# MicrocontrollerBoard_V0_0.net
KiCad netlist of a schematic drawn in EAGLE
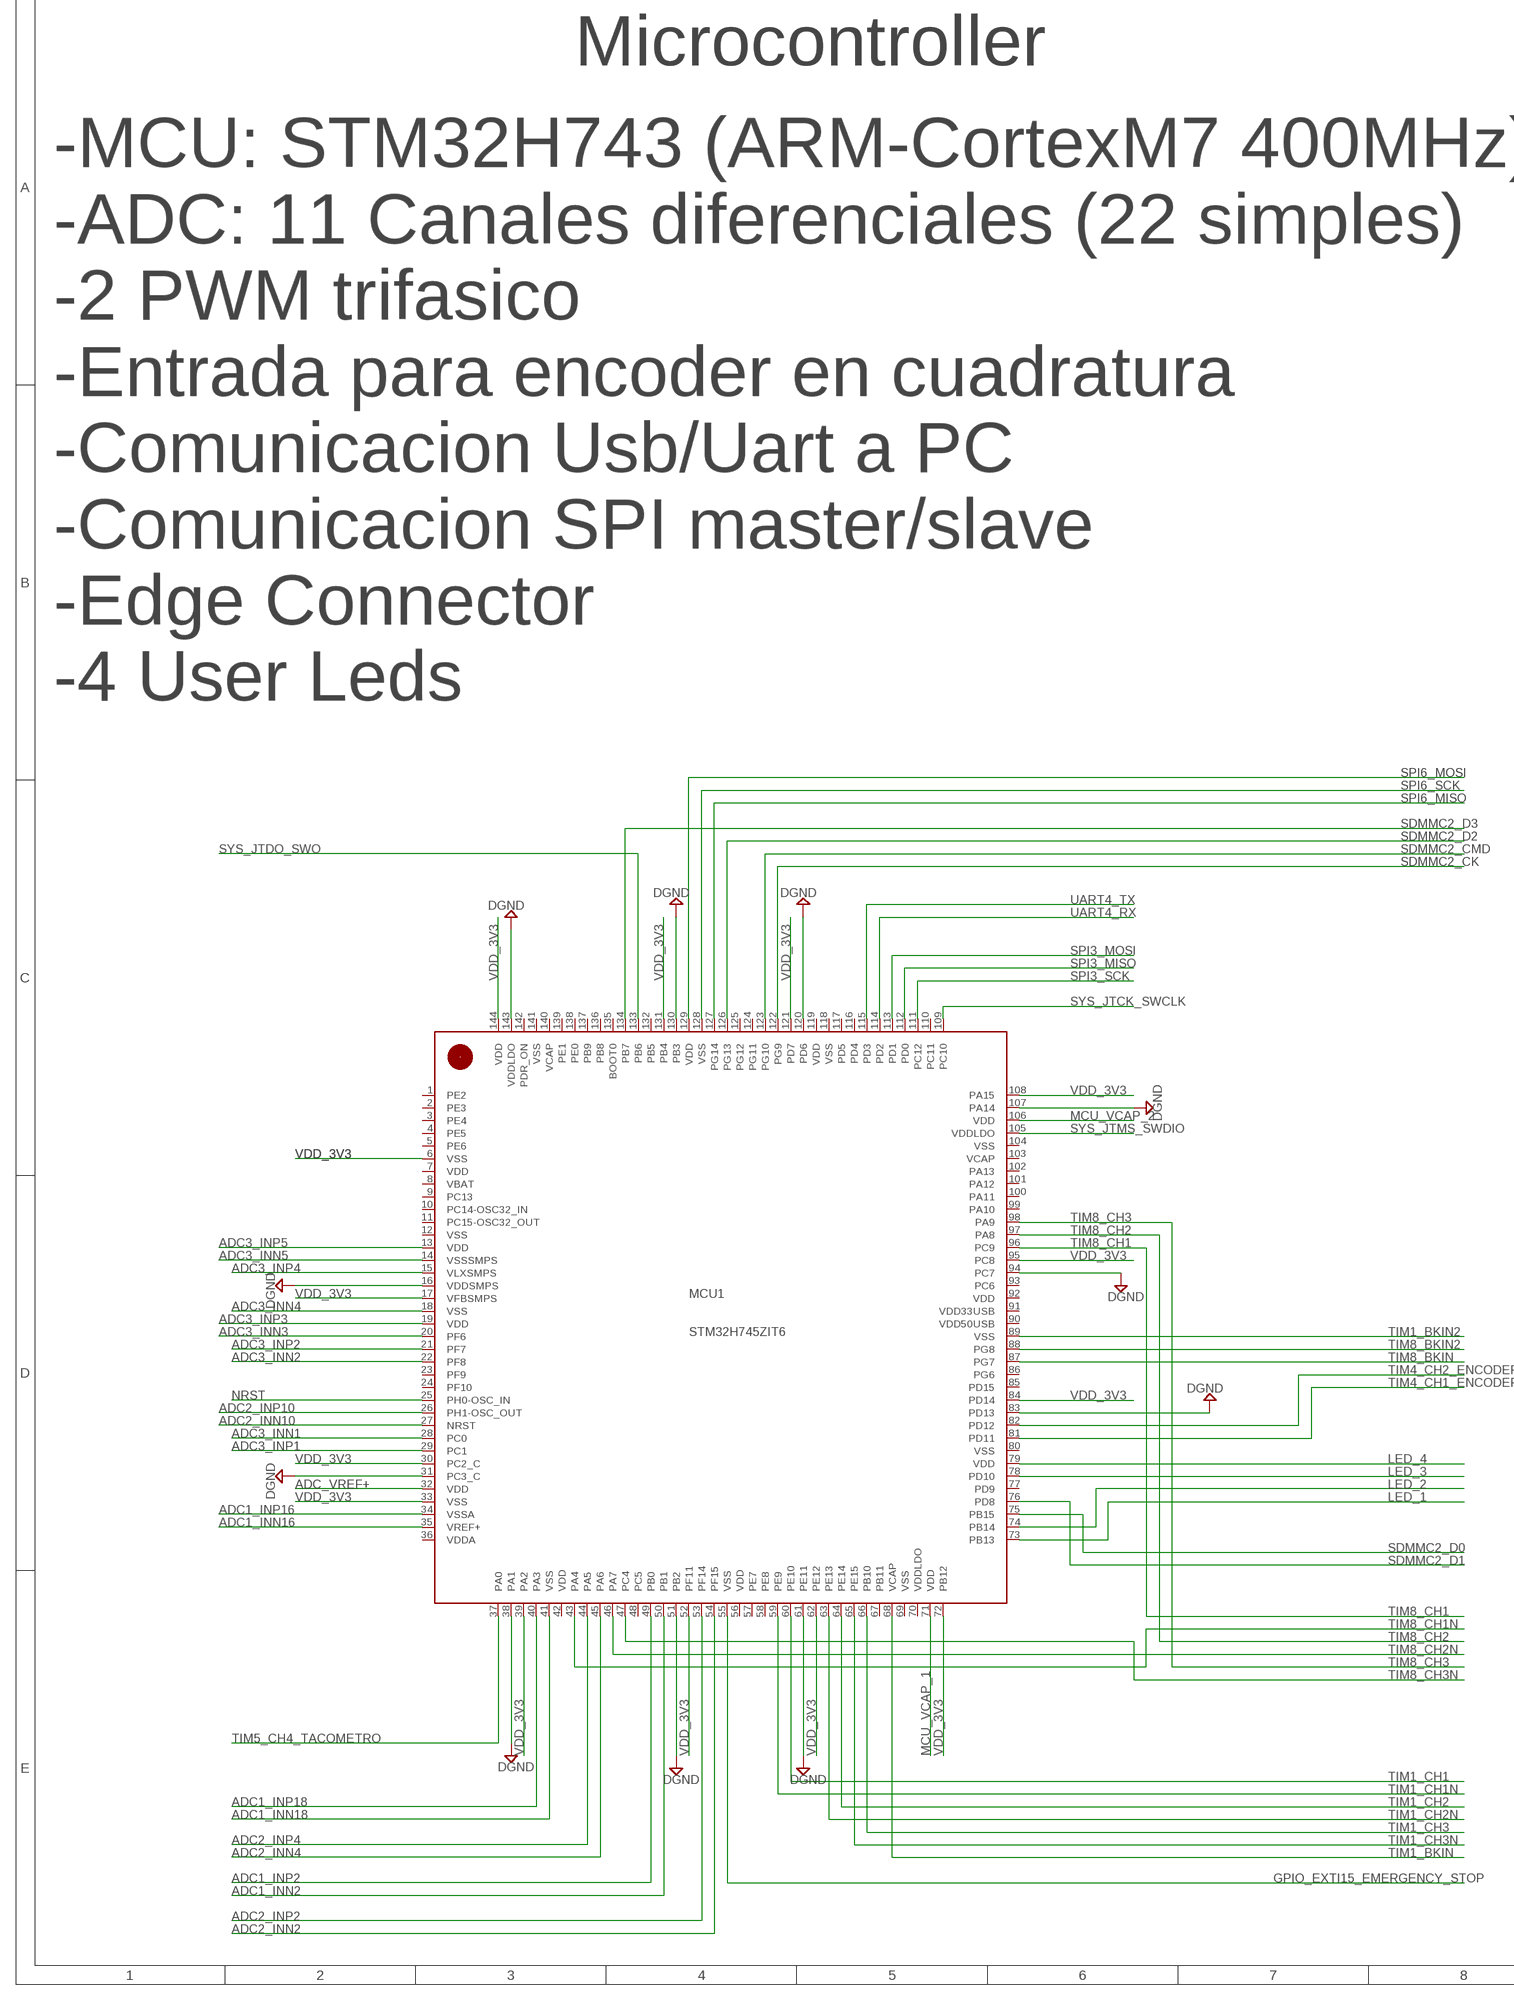
[diagram p0: schematic, sheet 1, part 1 of 2]
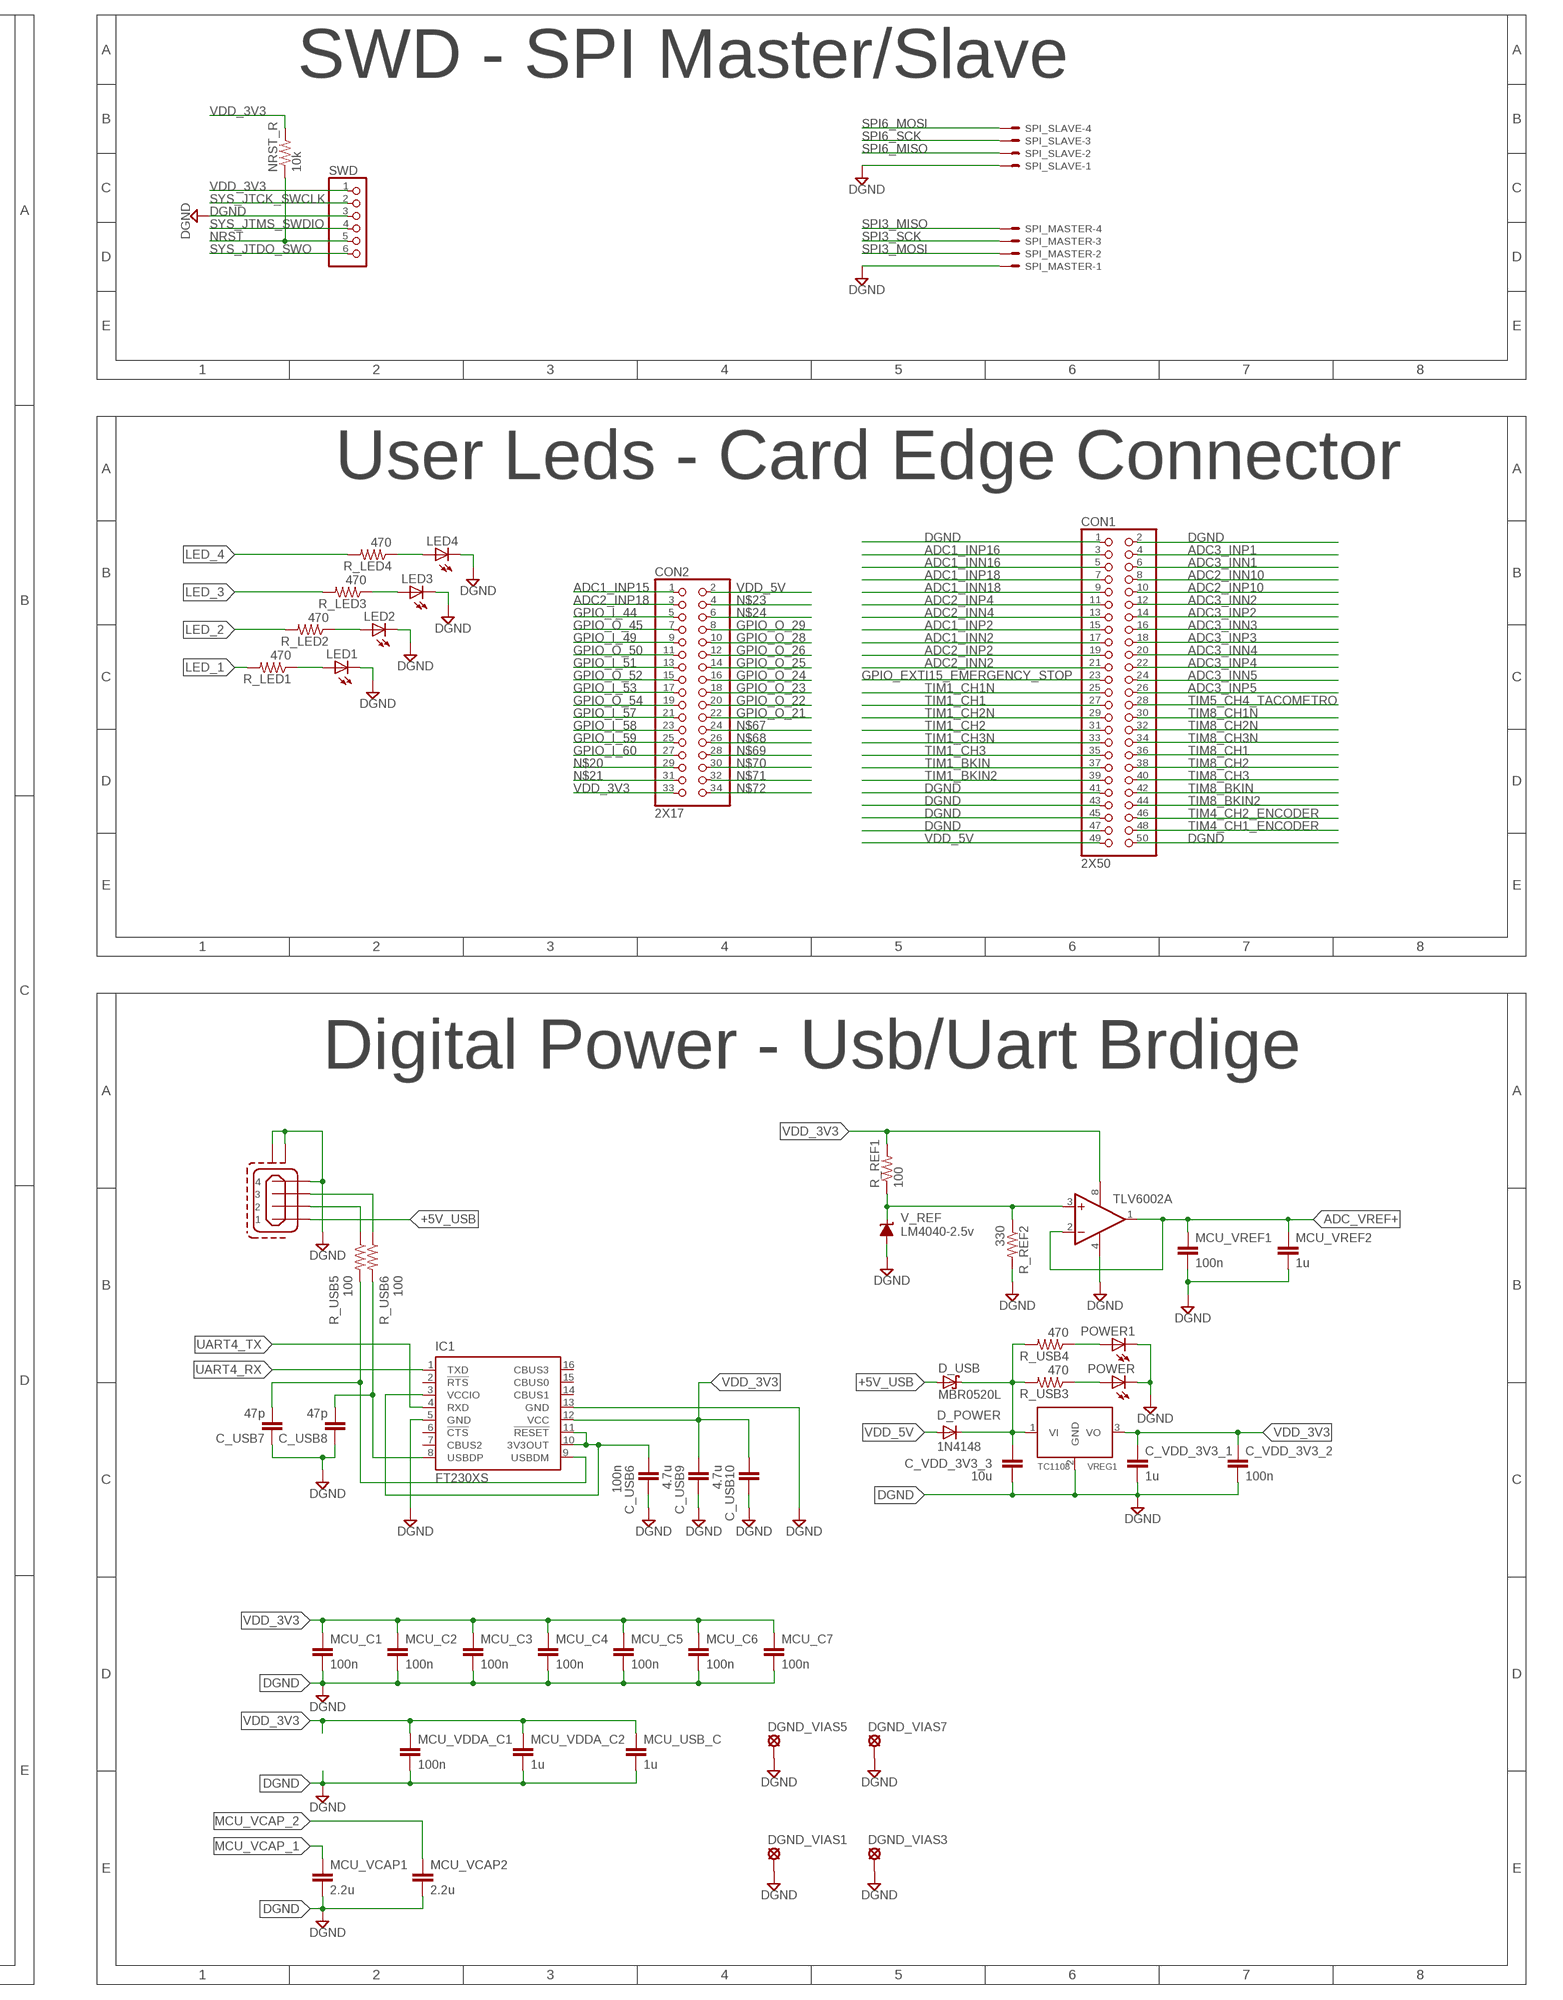
[diagram p1: schematic, sheet 1, part 2 of 2]

(export (version "E")
  (design (tool "Eeschema 10.0.6"))
  (components
    (comp (ref "CON1")
      (value "2X50")
      (footprint "eagle-import:2X25")
      (libsource (lib "eagle-import") (part "2X50"))
    )
    (comp (ref "CON2")
      (value "2X17")
      (footprint "eagle-import:2X17")
      (libsource (lib "eagle-import") (part "2X17"))
    )
    (comp (ref "C_USB6")
      (value "100n")
      (footprint "eagle-import:C0402")
      (libsource (lib "eagle-import") (part "C-EUC0402"))
    )
    (comp (ref "C_USB7")
      (value "47p")
      (footprint "eagle-import:C0402")
      (libsource (lib "eagle-import") (part "C-EUC0402"))
    )
    (comp (ref "C_USB8")
      (value "47p")
      (footprint "eagle-import:C0402")
      (libsource (lib "eagle-import") (part "C-EUC0402"))
    )
    (comp (ref "C_USB9")
      (value "4.7u")
      (footprint "eagle-import:C0402")
      (libsource (lib "eagle-import") (part "C-EUC0402"))
    )
    (comp (ref "C_USB10")
      (value "4.7u")
      (footprint "eagle-import:C0402")
      (libsource (lib "eagle-import") (part "C-EUC0402"))
    )
    (comp (ref "C_VDD_3V3_1")
      (value "1u")
      (footprint "eagle-import:C0603K")
      (libsource (lib "eagle-import") (part "C-EUC0603K"))
    )
    (comp (ref "C_VDD_3V3_2")
      (value "100n")
      (footprint "eagle-import:C0603K")
      (libsource (lib "eagle-import") (part "C-EUC0603K"))
    )
    (comp (ref "C_VDD_3V3_3")
      (value "10u")
      (footprint "eagle-import:C0603K")
      (libsource (lib "eagle-import") (part "C-EUC0603K"))
    )
    (comp (ref "DGND_VIAS1")
      (value "LSP10")
      (footprint "eagle-import:LSP10")
      (libsource (lib "eagle-import") (part "LSP10"))
    )
    (comp (ref "DGND_VIAS3")
      (value "LSP10")
      (footprint "eagle-import:LSP10")
      (libsource (lib "eagle-import") (part "LSP10"))
    )
    (comp (ref "DGND_VIAS5")
      (value "LSP10")
      (footprint "eagle-import:LSP10")
      (libsource (lib "eagle-import") (part "LSP10"))
    )
    (comp (ref "DGND_VIAS7")
      (value "LSP10")
      (footprint "eagle-import:LSP10")
      (libsource (lib "eagle-import") (part "LSP10"))
    )
    (comp (ref "D_POWER")
      (value "1N4148")
      (footprint "eagle-import:SMA-DO214AC")
      (libsource (lib "eagle-import") (part "GF1"))
    )
    (comp (ref "D_USB")
      (value "MBR0520L")
      (footprint "eagle-import:SOD-123")
      (libsource (lib "eagle-import") (part "MBR0520L"))
    )
    (comp (ref "IC1")
      (value "FT230XS")
      (footprint "eagle-import:SSOP16")
      (libsource (lib "eagle-import") (part "FT230XS"))
    )
    (comp (ref "LED1")
      (value "LEDCHIPLED_0805")
      (footprint "eagle-import:CHIPLED_0805")
      (libsource (lib "eagle-import") (part "LEDCHIPLED_0805"))
    )
    (comp (ref "LED2")
      (value "LEDCHIPLED_0805")
      (footprint "eagle-import:CHIPLED_0805")
      (libsource (lib "eagle-import") (part "LEDCHIPLED_0805"))
    )
    (comp (ref "LED3")
      (value "LEDCHIPLED_0805")
      (footprint "eagle-import:CHIPLED_0805")
      (libsource (lib "eagle-import") (part "LEDCHIPLED_0805"))
    )
    (comp (ref "LED4")
      (value "LEDCHIPLED_0805")
      (footprint "eagle-import:CHIPLED_0805")
      (libsource (lib "eagle-import") (part "LEDCHIPLED_0805"))
    )
    (comp (ref "MCU1")
      (value "STM32H745ZIT6144")
      (footprint "eagle-import:LQFP144")
      (libsource (lib "eagle-import") (part "STM32H745ZIT6144"))
    )
    (comp (ref "MCU_C1")
      (value "100n")
      (footprint "eagle-import:C0402")
      (libsource (lib "eagle-import") (part "C-EUC0402"))
    )
    (comp (ref "MCU_C2")
      (value "100n")
      (footprint "eagle-import:C0402")
      (libsource (lib "eagle-import") (part "C-EUC0402"))
    )
    (comp (ref "MCU_C3")
      (value "100n")
      (footprint "eagle-import:C0402")
      (libsource (lib "eagle-import") (part "C-EUC0402"))
    )
    (comp (ref "MCU_C4")
      (value "100n")
      (footprint "eagle-import:C0402")
      (libsource (lib "eagle-import") (part "C-EUC0402"))
    )
    (comp (ref "MCU_C5")
      (value "100n")
      (footprint "eagle-import:C0402")
      (libsource (lib "eagle-import") (part "C-EUC0402"))
    )
    (comp (ref "MCU_C6")
      (value "100n")
      (footprint "eagle-import:C0402")
      (libsource (lib "eagle-import") (part "C-EUC0402"))
    )
    (comp (ref "MCU_C7")
      (value "100n")
      (footprint "eagle-import:C0402")
      (libsource (lib "eagle-import") (part "C-EUC0402"))
    )
    (comp (ref "MCU_USB_C")
      (value "1u")
      (footprint "eagle-import:C0402")
      (libsource (lib "eagle-import") (part "C-EUC0402"))
    )
    (comp (ref "MCU_VCAP1")
      (value "2.2u")
      (footprint "eagle-import:C0402")
      (libsource (lib "eagle-import") (part "C-EUC0402"))
    )
    (comp (ref "MCU_VCAP2")
      (value "2.2u")
      (footprint "eagle-import:C0402")
      (libsource (lib "eagle-import") (part "C-EUC0402"))
    )
    (comp (ref "MCU_VDDA_C1")
      (value "100n")
      (footprint "eagle-import:C0402")
      (libsource (lib "eagle-import") (part "C-EUC0402"))
    )
    (comp (ref "MCU_VDDA_C2")
      (value "1u")
      (footprint "eagle-import:C0402")
      (libsource (lib "eagle-import") (part "C-EUC0402"))
    )
    (comp (ref "MCU_VREF1")
      (value "100n")
      (footprint "eagle-import:C0402")
      (libsource (lib "eagle-import") (part "C-EUC0402"))
    )
    (comp (ref "MCU_VREF2")
      (value "1u")
      (footprint "eagle-import:C0402")
      (libsource (lib "eagle-import") (part "C-EUC0402"))
    )
    (comp (ref "NRST_R")
      (value "10k")
      (footprint "eagle-import:R0402")
      (libsource (lib "eagle-import") (part "R-US_R0402"))
    )
    (comp (ref "POWER")
      (value "LEDCHIPLED_0805")
      (footprint "eagle-import:CHIPLED_0805")
      (libsource (lib "eagle-import") (part "LEDCHIPLED_0805"))
    )
    (comp (ref "POWER1")
      (value "LEDCHIPLED_0805")
      (footprint "eagle-import:CHIPLED_0805")
      (libsource (lib "eagle-import") (part "LEDCHIPLED_0805"))
    )
    (comp (ref "R_LED1")
      (value "470")
      (footprint "eagle-import:R0402")
      (libsource (lib "eagle-import") (part "R-US_R0402"))
    )
    (comp (ref "R_LED2")
      (value "470")
      (footprint "eagle-import:R0402")
      (libsource (lib "eagle-import") (part "R-US_R0402"))
    )
    (comp (ref "R_LED3")
      (value "470")
      (footprint "eagle-import:R0402")
      (libsource (lib "eagle-import") (part "R-US_R0402"))
    )
    (comp (ref "R_LED4")
      (value "470")
      (footprint "eagle-import:R0402")
      (libsource (lib "eagle-import") (part "R-US_R0402"))
    )
    (comp (ref "R_REF1")
      (value "100")
      (footprint "eagle-import:R0805")
      (libsource (lib "eagle-import") (part "R-US_R0805"))
    )
    (comp (ref "R_REF2")
      (value "330")
      (footprint "eagle-import:R0805")
      (libsource (lib "eagle-import") (part "R-US_R0805"))
    )
    (comp (ref "R_USB3")
      (value "470")
      (footprint "eagle-import:R0402")
      (libsource (lib "eagle-import") (part "R-US_R0402"))
    )
    (comp (ref "R_USB4")
      (value "470")
      (footprint "eagle-import:R0402")
      (libsource (lib "eagle-import") (part "R-US_R0402"))
    )
    (comp (ref "R_USB5")
      (value "100")
      (footprint "eagle-import:R0402")
      (libsource (lib "eagle-import") (part "R-US_R0402"))
    )
    (comp (ref "R_USB6")
      (value "100")
      (footprint "eagle-import:R0402")
      (libsource (lib "eagle-import") (part "R-US_R0402"))
    )
    (comp (ref "SPI_MASTER")
      (value "22-23-2041")
      (footprint "eagle-import:22-23-2041")
      (fields (field (name "MF") "MOLEX"))
      (libsource (lib "eagle-import") (part "22-23-2041"))
    )
    (comp (ref "SPI_SLAVE")
      (value "22-23-2041")
      (footprint "eagle-import:22-23-2041")
      (fields (field (name "MF") "MOLEX"))
      (libsource (lib "eagle-import") (part "22-23-2041"))
    )
    (comp (ref "SWD")
      (value "PINHD-1X6/90")
      (footprint "eagle-import:1X06_90")
      (libsource (lib "eagle-import") (part "PINHD-1X6/90"))
    )
    (comp (ref "TLV6002")
      (value "TL082D")
      (footprint "eagle-import:SO08")
      (libsource (lib "eagle-import") (part "TL082D"))
    )
    (comp (ref "VREG1")
      (value "TC1108'SOT-223'")
      (footprint "eagle-import:SOT-223")
      (libsource (lib "eagle-import") (part "TC1108'SOT-223'"))
    )
    (comp (ref "V_REF")
      (value "LM4040-2.5v")
      (footprint "eagle-import:DBZ_R-PDSO-G3")
      (fields (field (name "MPN") "LM4041A12IDBZR"))
      (libsource (lib "eagle-import") (part "LM4041DBZA12"))
    )
    (comp (ref "X2")
      (value "MINI-USB_SHIELD4P-85-32004-00X")
      (footprint "eagle-import:85-32004-00X")
      (libsource (lib "eagle-import") (part "MINI-USB_SHIELD4P-85-32004-00X"))
    )
  )
  (nets
    (net (code "1") (name "+5V_USB") (class "Default")
      (node (ref "D_USB") (pin "A") (pinfunction "IN_A") (pintype "passive"))
      (node (ref "X2") (pin "1") (pinfunction "1_1") (pintype "passive"))
    )
    (net (code "2") (name "/ADC1_INN2") (class "Default")
      (node (ref "CON1") (pin "17") (pinfunction "17_17") (pintype "passive"))
      (node (ref "MCU1") (pin "50") (pinfunction "PB1_50") (pintype "bidirectional"))
    )
    (net (code "3") (name "/ADC1_INN16") (class "Default")
      (node (ref "CON1") (pin "5") (pinfunction "5_5") (pintype "passive"))
      (node (ref "MCU1") (pin "35") (pinfunction "VREF+_35") (pintype "bidirectional"))
    )
    (net (code "4") (name "/ADC1_INN18") (class "Default")
      (node (ref "CON1") (pin "9") (pinfunction "9_9") (pintype "passive"))
      (node (ref "MCU1") (pin "41") (pinfunction "VSS_41") (pintype "bidirectional"))
    )
    (net (code "5") (name "/ADC1_INP2") (class "Default")
      (node (ref "CON1") (pin "15") (pinfunction "15_15") (pintype "passive"))
      (node (ref "MCU1") (pin "49") (pinfunction "PB0_49") (pintype "bidirectional"))
    )
    (net (code "6") (name "/ADC1_INP15") (class "Default")
      (node (ref "CON2") (pin "1") (pinfunction "1_1") (pintype "passive"))
    )
    (net (code "7") (name "/ADC1_INP16") (class "Default")
      (node (ref "CON1") (pin "3") (pinfunction "3_3") (pintype "passive"))
      (node (ref "MCU1") (pin "34") (pinfunction "VSSA_34") (pintype "bidirectional"))
    )
    (net (code "8") (name "/ADC1_INP18") (class "Default")
      (node (ref "CON1") (pin "7") (pinfunction "7_7") (pintype "passive"))
      (node (ref "MCU1") (pin "40") (pinfunction "PA3_40") (pintype "bidirectional"))
    )
    (net (code "9") (name "/ADC2_INN2") (class "Default")
      (node (ref "CON1") (pin "21") (pinfunction "21_21") (pintype "passive"))
      (node (ref "MCU1") (pin "54") (pinfunction "PF15_54") (pintype "bidirectional"))
    )
    (net (code "10") (name "/ADC2_INN4") (class "Default")
      (node (ref "CON1") (pin "13") (pinfunction "13_13") (pintype "passive"))
      (node (ref "MCU1") (pin "45") (pinfunction "PA6_45") (pintype "bidirectional"))
    )
    (net (code "11") (name "/ADC2_INN10") (class "Default")
      (node (ref "CON1") (pin "8") (pinfunction "8_8") (pintype "passive"))
      (node (ref "MCU1") (pin "27") (pinfunction "NRST_27") (pintype "bidirectional"))
    )
    (net (code "12") (name "/ADC2_INP2") (class "Default")
      (node (ref "CON1") (pin "19") (pinfunction "19_19") (pintype "passive"))
      (node (ref "MCU1") (pin "53") (pinfunction "PF14_53") (pintype "bidirectional"))
    )
    (net (code "13") (name "/ADC2_INP4") (class "Default")
      (node (ref "CON1") (pin "11") (pinfunction "11_11") (pintype "passive"))
      (node (ref "MCU1") (pin "44") (pinfunction "PA5_44") (pintype "bidirectional"))
    )
    (net (code "14") (name "/ADC2_INP10") (class "Default")
      (node (ref "CON1") (pin "10") (pinfunction "10_10") (pintype "passive"))
      (node (ref "MCU1") (pin "26") (pinfunction "PH1-OSC_OUT_26") (pintype "bidirectional"))
    )
    (net (code "15") (name "/ADC2_INP18") (class "Default")
      (node (ref "CON2") (pin "3") (pinfunction "3_3") (pintype "passive"))
    )
    (net (code "16") (name "/ADC3_INN1") (class "Default")
      (node (ref "CON1") (pin "6") (pinfunction "6_6") (pintype "passive"))
      (node (ref "MCU1") (pin "28") (pinfunction "PC0_28") (pintype "bidirectional"))
    )
    (net (code "17") (name "/ADC3_INN2") (class "Default")
      (node (ref "CON1") (pin "12") (pinfunction "12_12") (pintype "passive"))
      (node (ref "MCU1") (pin "22") (pinfunction "PF8_22") (pintype "bidirectional"))
    )
    (net (code "18") (name "/ADC3_INN3") (class "Default")
      (node (ref "CON1") (pin "16") (pinfunction "16_16") (pintype "passive"))
      (node (ref "MCU1") (pin "20") (pinfunction "PF6_20") (pintype "bidirectional"))
    )
    (net (code "19") (name "/ADC3_INN4") (class "Default")
      (node (ref "CON1") (pin "20") (pinfunction "20_20") (pintype "passive"))
      (node (ref "MCU1") (pin "18") (pinfunction "VSS_18") (pintype "bidirectional"))
    )
    (net (code "20") (name "/ADC3_INN5") (class "Default")
      (node (ref "CON1") (pin "24") (pinfunction "24_24") (pintype "passive"))
      (node (ref "MCU1") (pin "14") (pinfunction "VSSSMPS_14") (pintype "bidirectional"))
    )
    (net (code "21") (name "/ADC3_INP1") (class "Default")
      (node (ref "CON1") (pin "4") (pinfunction "4_4") (pintype "passive"))
      (node (ref "MCU1") (pin "29") (pinfunction "PC1_29") (pintype "bidirectional"))
    )
    (net (code "22") (name "/ADC3_INP2") (class "Default")
      (node (ref "CON1") (pin "14") (pinfunction "14_14") (pintype "passive"))
      (node (ref "MCU1") (pin "21") (pinfunction "PF7_21") (pintype "bidirectional"))
    )
    (net (code "23") (name "/ADC3_INP3") (class "Default")
      (node (ref "CON1") (pin "18") (pinfunction "18_18") (pintype "passive"))
      (node (ref "MCU1") (pin "19") (pinfunction "VDD_19") (pintype "bidirectional"))
    )
    (net (code "24") (name "/ADC3_INP4") (class "Default")
      (node (ref "CON1") (pin "22") (pinfunction "22_22") (pintype "passive"))
      (node (ref "MCU1") (pin "15") (pinfunction "VLXSMPS_15") (pintype "bidirectional"))
    )
    (net (code "25") (name "/ADC3_INP5") (class "Default")
      (node (ref "CON1") (pin "26") (pinfunction "26_26") (pintype "passive"))
      (node (ref "MCU1") (pin "13") (pinfunction "VDD_13") (pintype "bidirectional"))
    )
    (net (code "26") (name "/GPIO_EXTI15_EMERGENCY_STOP") (class "Default")
      (node (ref "CON1") (pin "23") (pinfunction "23_23") (pintype "passive"))
      (node (ref "MCU1") (pin "55") (pinfunction "VSS_55") (pintype "bidirectional"))
    )
    (net (code "27") (name "/GPIO_I_44") (class "Default")
      (node (ref "CON2") (pin "5") (pinfunction "5_5") (pintype "passive"))
    )
    (net (code "28") (name "/GPIO_I_49") (class "Default")
      (node (ref "CON2") (pin "9") (pinfunction "9_9") (pintype "passive"))
    )
    (net (code "29") (name "/GPIO_I_51") (class "Default")
      (node (ref "CON2") (pin "13") (pinfunction "13_13") (pintype "passive"))
    )
    (net (code "30") (name "/GPIO_I_53") (class "Default")
      (node (ref "CON2") (pin "17") (pinfunction "17_17") (pintype "passive"))
    )
    (net (code "31") (name "/GPIO_I_57") (class "Default")
      (node (ref "CON2") (pin "21") (pinfunction "21_21") (pintype "passive"))
    )
    (net (code "32") (name "/GPIO_I_58") (class "Default")
      (node (ref "CON2") (pin "23") (pinfunction "23_23") (pintype "passive"))
    )
    (net (code "33") (name "/GPIO_I_59") (class "Default")
      (node (ref "CON2") (pin "25") (pinfunction "25_25") (pintype "passive"))
    )
    (net (code "34") (name "/GPIO_I_60") (class "Default")
      (node (ref "CON2") (pin "27") (pinfunction "27_27") (pintype "passive"))
    )
    (net (code "35") (name "/GPIO_O_21") (class "Default")
      (node (ref "CON2") (pin "22") (pinfunction "22_22") (pintype "passive"))
    )
    (net (code "36") (name "/GPIO_O_22") (class "Default")
      (node (ref "CON2") (pin "20") (pinfunction "20_20") (pintype "passive"))
    )
    (net (code "37") (name "/GPIO_O_23") (class "Default")
      (node (ref "CON2") (pin "18") (pinfunction "18_18") (pintype "passive"))
    )
    (net (code "38") (name "/GPIO_O_24") (class "Default")
      (node (ref "CON2") (pin "16") (pinfunction "16_16") (pintype "passive"))
    )
    (net (code "39") (name "/GPIO_O_25") (class "Default")
      (node (ref "CON2") (pin "14") (pinfunction "14_14") (pintype "passive"))
    )
    (net (code "40") (name "/GPIO_O_26") (class "Default")
      (node (ref "CON2") (pin "12") (pinfunction "12_12") (pintype "passive"))
    )
    (net (code "41") (name "/GPIO_O_28") (class "Default")
      (node (ref "CON2") (pin "10") (pinfunction "10_10") (pintype "passive"))
    )
    (net (code "42") (name "/GPIO_O_29") (class "Default")
      (node (ref "CON2") (pin "8") (pinfunction "8_8") (pintype "passive"))
    )
    (net (code "43") (name "/GPIO_O_45") (class "Default")
      (node (ref "CON2") (pin "7") (pinfunction "7_7") (pintype "passive"))
    )
    (net (code "44") (name "/GPIO_O_50") (class "Default")
      (node (ref "CON2") (pin "11") (pinfunction "11_11") (pintype "passive"))
    )
    (net (code "45") (name "/GPIO_O_52") (class "Default")
      (node (ref "CON2") (pin "15") (pinfunction "15_15") (pintype "passive"))
    )
    (net (code "46") (name "/GPIO_O_54") (class "Default")
      (node (ref "CON2") (pin "19") (pinfunction "19_19") (pintype "passive"))
    )
    (net (code "47") (name "/N$20") (class "Default")
      (node (ref "CON2") (pin "29") (pinfunction "29_29") (pintype "passive"))
    )
    (net (code "48") (name "/N$21") (class "Default")
      (node (ref "CON2") (pin "31") (pinfunction "31_31") (pintype "passive"))
    )
    (net (code "49") (name "/N$23") (class "Default")
      (node (ref "CON2") (pin "4") (pinfunction "4_4") (pintype "passive"))
    )
    (net (code "50") (name "/N$24") (class "Default")
      (node (ref "CON2") (pin "6") (pinfunction "6_6") (pintype "passive"))
    )
    (net (code "51") (name "/N$67") (class "Default")
      (node (ref "CON2") (pin "24") (pinfunction "24_24") (pintype "passive"))
    )
    (net (code "52") (name "/N$68") (class "Default")
      (node (ref "CON2") (pin "26") (pinfunction "26_26") (pintype "passive"))
    )
    (net (code "53") (name "/N$69") (class "Default")
      (node (ref "CON2") (pin "28") (pinfunction "28_28") (pintype "passive"))
    )
    (net (code "54") (name "/N$70") (class "Default")
      (node (ref "CON2") (pin "30") (pinfunction "30_30") (pintype "passive"))
    )
    (net (code "55") (name "/N$71") (class "Default")
      (node (ref "CON2") (pin "32") (pinfunction "32_32") (pintype "passive"))
    )
    (net (code "56") (name "/N$72") (class "Default")
      (node (ref "CON2") (pin "34") (pinfunction "34_34") (pintype "passive"))
    )
    (net (code "57") (name "/NRST") (class "Default")
      (node (ref "MCU1") (pin "25") (pinfunction "PH0-OSC_IN_25") (pintype "bidirectional"))
      (node (ref "NRST_R") (pin "1") (pinfunction "1_1") (pintype "passive"))
      (node (ref "SWD") (pin "5") (pinfunction "5_5") (pintype "passive"))
    )
    (net (code "58") (name "/SDMMC2_CK") (class "Default")
      (node (ref "MCU1") (pin "122") (pinfunction "PG9_122") (pintype "bidirectional"))
    )
    (net (code "59") (name "/SDMMC2_CMD") (class "Default")
      (node (ref "MCU1") (pin "123") (pinfunction "PG10_123") (pintype "bidirectional"))
    )
    (net (code "60") (name "/SDMMC2_D0") (class "Default")
      (node (ref "MCU1") (pin "75") (pinfunction "PB15_75") (pintype "bidirectional"))
    )
    (net (code "61") (name "/SDMMC2_D1") (class "Default")
      (node (ref "MCU1") (pin "76") (pinfunction "PD8_76") (pintype "bidirectional"))
    )
    (net (code "62") (name "/SDMMC2_D2") (class "Default")
      (node (ref "MCU1") (pin "126") (pinfunction "PG13_126") (pintype "bidirectional"))
    )
    (net (code "63") (name "/SDMMC2_D3") (class "Default")
      (node (ref "MCU1") (pin "134") (pinfunction "PB7_134") (pintype "bidirectional"))
    )
    (net (code "64") (name "/SPI3_MISO") (class "Default")
      (node (ref "MCU1") (pin "112") (pinfunction "PD0_112") (pintype "bidirectional"))
      (node (ref "SPI_MASTER") (pin "4") (pinfunction "S_4") (pintype "passive"))
    )
    (net (code "65") (name "/SPI3_MOSI") (class "Default")
      (node (ref "MCU1") (pin "113") (pinfunction "PD1_113") (pintype "bidirectional"))
      (node (ref "SPI_MASTER") (pin "2") (pinfunction "S_2") (pintype "passive"))
    )
    (net (code "66") (name "/SPI3_SCK") (class "Default")
      (node (ref "MCU1") (pin "111") (pinfunction "PC12_111") (pintype "bidirectional"))
      (node (ref "SPI_MASTER") (pin "3") (pinfunction "S_3") (pintype "passive"))
    )
    (net (code "67") (name "/SPI6_MISO") (class "Default")
      (node (ref "MCU1") (pin "127") (pinfunction "PG14_127") (pintype "bidirectional"))
      (node (ref "SPI_SLAVE") (pin "2") (pinfunction "S_2") (pintype "passive"))
    )
    (net (code "68") (name "/SPI6_MOSI") (class "Default")
      (node (ref "MCU1") (pin "129") (pinfunction "VDD_129") (pintype "bidirectional"))
      (node (ref "SPI_SLAVE") (pin "4") (pinfunction "S_4") (pintype "passive"))
    )
    (net (code "69") (name "/SPI6_SCK") (class "Default")
      (node (ref "MCU1") (pin "128") (pinfunction "VSS_128") (pintype "bidirectional"))
      (node (ref "SPI_SLAVE") (pin "3") (pinfunction "S_3") (pintype "passive"))
    )
    (net (code "70") (name "/SYS_JTCK_SWCLK") (class "Default")
      (node (ref "MCU1") (pin "109") (pinfunction "PC10_109") (pintype "bidirectional"))
      (node (ref "SWD") (pin "2") (pinfunction "2_2") (pintype "passive"))
    )
    (net (code "71") (name "/SYS_JTDO_SWO") (class "Default")
      (node (ref "MCU1") (pin "133") (pinfunction "PB6_133") (pintype "bidirectional"))
      (node (ref "SWD") (pin "6") (pinfunction "6_6") (pintype "passive"))
    )
    (net (code "72") (name "/SYS_JTMS_SWDIO") (class "Default")
      (node (ref "MCU1") (pin "105") (pinfunction "VDDLDO_105") (pintype "bidirectional"))
      (node (ref "SWD") (pin "4") (pinfunction "4_4") (pintype "passive"))
    )
    (net (code "73") (name "/TIM1_BKIN") (class "Default")
      (node (ref "CON1") (pin "37") (pinfunction "37_37") (pintype "passive"))
      (node (ref "MCU1") (pin "68") (pinfunction "VCAP_68") (pintype "bidirectional"))
    )
    (net (code "74") (name "/TIM1_BKIN2") (class "Default")
      (node (ref "CON1") (pin "39") (pinfunction "39_39") (pintype "passive"))
      (node (ref "MCU1") (pin "89") (pinfunction "VSS_89") (pintype "bidirectional"))
    )
    (net (code "75") (name "/TIM1_CH1") (class "Default")
      (node (ref "CON1") (pin "27") (pinfunction "27_27") (pintype "passive"))
      (node (ref "MCU1") (pin "60") (pinfunction "PE10_60") (pintype "bidirectional"))
    )
    (net (code "76") (name "/TIM1_CH1N") (class "Default")
      (node (ref "CON1") (pin "25") (pinfunction "25_25") (pintype "passive"))
      (node (ref "MCU1") (pin "59") (pinfunction "PE9_59") (pintype "bidirectional"))
    )
    (net (code "77") (name "/TIM1_CH2") (class "Default")
      (node (ref "CON1") (pin "31") (pinfunction "31_31") (pintype "passive"))
      (node (ref "MCU1") (pin "64") (pinfunction "PE14_64") (pintype "bidirectional"))
    )
    (net (code "78") (name "/TIM1_CH2N") (class "Default")
      (node (ref "CON1") (pin "29") (pinfunction "29_29") (pintype "passive"))
      (node (ref "MCU1") (pin "63") (pinfunction "PE13_63") (pintype "bidirectional"))
    )
    (net (code "79") (name "/TIM1_CH3") (class "Default")
      (node (ref "CON1") (pin "35") (pinfunction "35_35") (pintype "passive"))
      (node (ref "MCU1") (pin "66") (pinfunction "PB10_66") (pintype "bidirectional"))
    )
    (net (code "80") (name "/TIM1_CH3N") (class "Default")
      (node (ref "CON1") (pin "33") (pinfunction "33_33") (pintype "passive"))
      (node (ref "MCU1") (pin "65") (pinfunction "PE15_65") (pintype "bidirectional"))
    )
    (net (code "81") (name "/TIM4_CH1_ENCODER") (class "Default")
      (node (ref "CON1") (pin "48") (pinfunction "48_48") (pintype "passive"))
      (node (ref "MCU1") (pin "81") (pinfunction "PD11_81") (pintype "bidirectional"))
    )
    (net (code "82") (name "/TIM4_CH2_ENCODER") (class "Default")
      (node (ref "CON1") (pin "46") (pinfunction "46_46") (pintype "passive"))
      (node (ref "MCU1") (pin "82") (pinfunction "PD12_82") (pintype "bidirectional"))
    )
    (net (code "83") (name "/TIM5_CH4_TACOMETRO") (class "Default")
      (node (ref "CON1") (pin "28") (pinfunction "28_28") (pintype "passive"))
      (node (ref "MCU1") (pin "37") (pinfunction "PA0_37") (pintype "bidirectional"))
    )
    (net (code "84") (name "/TIM8_BKIN") (class "Default")
      (node (ref "CON1") (pin "42") (pinfunction "42_42") (pintype "passive"))
      (node (ref "MCU1") (pin "87") (pinfunction "PG7_87") (pintype "bidirectional"))
    )
    (net (code "85") (name "/TIM8_BKIN2") (class "Default")
      (node (ref "CON1") (pin "44") (pinfunction "44_44") (pintype "passive"))
      (node (ref "MCU1") (pin "88") (pinfunction "PG8_88") (pintype "bidirectional"))
    )
    (net (code "86") (name "/TIM8_CH1") (class "Default")
      (node (ref "CON1") (pin "36") (pinfunction "36_36") (pintype "passive"))
      (node (ref "MCU1") (pin "96") (pinfunction "PC9_96") (pintype "bidirectional"))
    )
    (net (code "87") (name "/TIM8_CH1N") (class "Default")
      (node (ref "CON1") (pin "30") (pinfunction "30_30") (pintype "passive"))
      (node (ref "MCU1") (pin "43") (pinfunction "PA4_43") (pintype "bidirectional"))
    )
    (net (code "88") (name "/TIM8_CH2") (class "Default")
      (node (ref "CON1") (pin "38") (pinfunction "38_38") (pintype "passive"))
      (node (ref "MCU1") (pin "97") (pinfunction "PA8_97") (pintype "bidirectional"))
    )
    (net (code "89") (name "/TIM8_CH2N") (class "Default")
      (node (ref "CON1") (pin "32") (pinfunction "32_32") (pintype "passive"))
      (node (ref "MCU1") (pin "46") (pinfunction "PA7_46") (pintype "bidirectional"))
    )
    (net (code "90") (name "/TIM8_CH3") (class "Default")
      (node (ref "CON1") (pin "40") (pinfunction "40_40") (pintype "passive"))
      (node (ref "MCU1") (pin "98") (pinfunction "PA9_98") (pintype "bidirectional"))
    )
    (net (code "91") (name "/TIM8_CH3N") (class "Default")
      (node (ref "CON1") (pin "34") (pinfunction "34_34") (pintype "passive"))
      (node (ref "MCU1") (pin "47") (pinfunction "PC4_47") (pintype "bidirectional"))
    )
    (net (code "92") (name "ADC_VREF+") (class "Default")
      (node (ref "MCU1") (pin "32") (pinfunction "VDD_32") (pintype "bidirectional"))
      (node (ref "MCU_VREF1") (pin "1") (pinfunction "1_1") (pintype "passive"))
      (node (ref "MCU_VREF2") (pin "1") (pinfunction "1_1") (pintype "passive"))
      (node (ref "TLV6002") (pin "1") (pinfunction "OUT_1") (pintype "output"))
      (node (ref "TLV6002") (pin "2") (pinfunction "-IN_2") (pintype "input"))
    )
    (net (code "93") (name "DGND") (class "Default")
      (node (ref "CON1") (pin "1") (pinfunction "1_1") (pintype "passive"))
      (node (ref "CON1") (pin "2") (pinfunction "2_2") (pintype "passive"))
      (node (ref "CON1") (pin "41") (pinfunction "41_41") (pintype "passive"))
      (node (ref "CON1") (pin "43") (pinfunction "43_43") (pintype "passive"))
      (node (ref "CON1") (pin "45") (pinfunction "45_45") (pintype "passive"))
      (node (ref "CON1") (pin "47") (pinfunction "47_47") (pintype "passive"))
      (node (ref "CON1") (pin "50") (pinfunction "50_50") (pintype "passive"))
      (node (ref "C_USB10") (pin "1") (pinfunction "1_1") (pintype "passive"))
      (node (ref "C_USB6") (pin "1") (pinfunction "1_1") (pintype "passive"))
      (node (ref "C_USB7") (pin "1") (pinfunction "1_1") (pintype "passive"))
      (node (ref "C_USB8") (pin "1") (pinfunction "1_1") (pintype "passive"))
      (node (ref "C_USB9") (pin "1") (pinfunction "1_1") (pintype "passive"))
      (node (ref "C_VDD_3V3_1") (pin "2") (pinfunction "2_2") (pintype "passive"))
      (node (ref "C_VDD_3V3_2") (pin "2") (pinfunction "2_2") (pintype "passive"))
      (node (ref "C_VDD_3V3_3") (pin "2") (pinfunction "2_2") (pintype "passive"))
      (node (ref "DGND_VIAS1") (pin "MP") (pinfunction "MP_MP") (pintype "passive"))
      (node (ref "DGND_VIAS3") (pin "MP") (pinfunction "MP_MP") (pintype "passive"))
      (node (ref "DGND_VIAS5") (pin "MP") (pinfunction "MP_MP") (pintype "passive"))
      (node (ref "DGND_VIAS7") (pin "MP") (pinfunction "MP_MP") (pintype "passive"))
      (node (ref "IC1") (pin "13") (pinfunction "GND_13") (pintype "power_in"))
      (node (ref "IC1") (pin "5") (pinfunction "GND_5") (pintype "power_in"))
      (node (ref "LED1") (pin "C") (pinfunction "C_C") (pintype "passive"))
      (node (ref "LED2") (pin "C") (pinfunction "C_C") (pintype "passive"))
      (node (ref "LED3") (pin "C") (pinfunction "C_C") (pintype "passive"))
      (node (ref "LED4") (pin "C") (pinfunction "C_C") (pintype "passive"))
      (node (ref "MCU1") (pin "107") (pinfunction "PA14_107") (pintype "bidirectional"))
      (node (ref "MCU1") (pin "120") (pinfunction "PD6_120") (pintype "bidirectional"))
      (node (ref "MCU1") (pin "130") (pinfunction "PB3_130") (pintype "bidirectional"))
      (node (ref "MCU1") (pin "143") (pinfunction "VDDLDO_143") (pintype "bidirectional"))
      (node (ref "MCU1") (pin "16") (pinfunction "VDDSMPS_16") (pintype "bidirectional"))
      (node (ref "MCU1") (pin "31") (pinfunction "PC3_C_31") (pintype "bidirectional"))
      (node (ref "MCU1") (pin "38") (pinfunction "PA1_38") (pintype "bidirectional"))
      (node (ref "MCU1") (pin "51") (pinfunction "PB2_51") (pintype "bidirectional"))
      (node (ref "MCU1") (pin "61") (pinfunction "PE11_61") (pintype "bidirectional"))
      (node (ref "MCU1") (pin "83") (pinfunction "PD13_83") (pintype "bidirectional"))
      (node (ref "MCU1") (pin "94") (pinfunction "PC7_94") (pintype "bidirectional"))
      (node (ref "MCU_C1") (pin "2") (pinfunction "2_2") (pintype "passive"))
      (node (ref "MCU_C2") (pin "2") (pinfunction "2_2") (pintype "passive"))
      (node (ref "MCU_C3") (pin "2") (pinfunction "2_2") (pintype "passive"))
      (node (ref "MCU_C4") (pin "2") (pinfunction "2_2") (pintype "passive"))
      (node (ref "MCU_C5") (pin "2") (pinfunction "2_2") (pintype "passive"))
      (node (ref "MCU_C6") (pin "2") (pinfunction "2_2") (pintype "passive"))
      (node (ref "MCU_C7") (pin "2") (pinfunction "2_2") (pintype "passive"))
      (node (ref "MCU_USB_C") (pin "2") (pinfunction "2_2") (pintype "passive"))
      (node (ref "MCU_VCAP1") (pin "2") (pinfunction "2_2") (pintype "passive"))
      (node (ref "MCU_VCAP2") (pin "2") (pinfunction "2_2") (pintype "passive"))
      (node (ref "MCU_VDDA_C1") (pin "2") (pinfunction "2_2") (pintype "passive"))
      (node (ref "MCU_VDDA_C2") (pin "2") (pinfunction "2_2") (pintype "passive"))
      (node (ref "MCU_VREF1") (pin "2") (pinfunction "2_2") (pintype "passive"))
      (node (ref "MCU_VREF2") (pin "2") (pinfunction "2_2") (pintype "passive"))
      (node (ref "POWER") (pin "C") (pinfunction "C_C") (pintype "passive"))
      (node (ref "POWER1") (pin "C") (pinfunction "C_C") (pintype "passive"))
      (node (ref "R_REF2") (pin "2") (pinfunction "2_2") (pintype "passive"))
      (node (ref "SPI_MASTER") (pin "1") (pinfunction "S_1") (pintype "passive"))
      (node (ref "SPI_SLAVE") (pin "1") (pinfunction "S_1") (pintype "passive"))
      (node (ref "SWD") (pin "3") (pinfunction "3_3") (pintype "passive"))
      (node (ref "TLV6002") (pin "4") (pinfunction "V-_4") (pintype "power_in"))
      (node (ref "VREG1") (pin "2") (pinfunction "GND_2") (pintype "bidirectional"))
      (node (ref "V_REF") (pin "2") (pinfunction "A_2") (pintype "passive"))
      (node (ref "X2") (pin "4") (pinfunction "4_4") (pintype "passive"))
      (node (ref "X2") (pin "M1") (pinfunction "S1_M1") (pintype "passive"))
      (node (ref "X2") (pin "M2") (pinfunction "S2_M2") (pintype "passive"))
    )
    (net (code "94") (name "LED_1") (class "Default")
      (node (ref "MCU1") (pin "73") (pinfunction "PB13_73") (pintype "bidirectional"))
      (node (ref "R_LED1") (pin "2") (pinfunction "2_2") (pintype "passive"))
    )
    (net (code "95") (name "LED_2") (class "Default")
      (node (ref "MCU1") (pin "74") (pinfunction "PB14_74") (pintype "bidirectional"))
      (node (ref "R_LED2") (pin "2") (pinfunction "2_2") (pintype "passive"))
    )
    (net (code "96") (name "LED_3") (class "Default")
      (node (ref "MCU1") (pin "78") (pinfunction "PD10_78") (pintype "bidirectional"))
      (node (ref "R_LED3") (pin "2") (pinfunction "2_2") (pintype "passive"))
    )
    (net (code "97") (name "LED_4") (class "Default")
      (node (ref "MCU1") (pin "79") (pinfunction "VDD_79") (pintype "bidirectional"))
      (node (ref "R_LED4") (pin "2") (pinfunction "2_2") (pintype "passive"))
    )
    (net (code "98") (name "MCU_VCAP_1") (class "Default")
      (node (ref "MCU1") (pin "71") (pinfunction "VDD_71") (pintype "bidirectional"))
      (node (ref "MCU_VCAP1") (pin "1") (pinfunction "1_1") (pintype "passive"))
    )
    (net (code "99") (name "MCU_VCAP_2") (class "Default")
      (node (ref "MCU1") (pin "106") (pinfunction "VDD_106") (pintype "bidirectional"))
      (node (ref "MCU_VCAP2") (pin "1") (pinfunction "1_1") (pintype "passive"))
    )
    (net (code "100") (name "Net-(D_POWER-C)") (class "Default")
      (node (ref "C_VDD_3V3_3") (pin "1") (pinfunction "1_1") (pintype "passive"))
      (node (ref "D_POWER") (pin "K") (pinfunction "C_K") (pintype "passive"))
      (node (ref "D_USB") (pin "C") (pinfunction "OUT_C") (pintype "passive"))
      (node (ref "R_USB3") (pin "2") (pinfunction "2_2") (pintype "passive"))
      (node (ref "R_USB4") (pin "2") (pinfunction "2_2") (pintype "passive"))
      (node (ref "VREG1") (pin "1") (pinfunction "VI_1") (pintype "bidirectional"))
    )
    (net (code "101") (name "Net-(IC1-3V3OUT)") (class "Default")
      (node (ref "C_USB6") (pin "2") (pinfunction "2_2") (pintype "passive"))
      (node (ref "IC1") (pin "10") (pinfunction "3V3OUT_10") (pintype "output"))
      (node (ref "IC1") (pin "11") (pinfunction "~{RESET}_11") (pintype "input"))
      (node (ref "IC1") (pin "3") (pinfunction "VCCIO_3") (pintype "power_in"))
    )
    (net (code "102") (name "Net-(IC1-USBDM)") (class "Default")
      (node (ref "C_USB7") (pin "2") (pinfunction "2_2") (pintype "passive"))
      (node (ref "IC1") (pin "9") (pinfunction "USBDM_9") (pintype "input"))
      (node (ref "R_USB5") (pin "2") (pinfunction "2_2") (pintype "passive"))
    )
    (net (code "103") (name "Net-(IC1-USBDP)") (class "Default")
      (node (ref "C_USB8") (pin "2") (pinfunction "2_2") (pintype "passive"))
      (node (ref "IC1") (pin "8") (pinfunction "USBDP_8") (pintype "input"))
      (node (ref "R_USB6") (pin "2") (pinfunction "2_2") (pintype "passive"))
    )
    (net (code "104") (name "Net-(LED1-PadA)") (class "Default")
      (node (ref "LED1") (pin "A") (pinfunction "A_A") (pintype "passive"))
      (node (ref "R_LED1") (pin "1") (pinfunction "1_1") (pintype "passive"))
    )
    (net (code "105") (name "Net-(LED2-PadA)") (class "Default")
      (node (ref "LED2") (pin "A") (pinfunction "A_A") (pintype "passive"))
      (node (ref "R_LED2") (pin "1") (pinfunction "1_1") (pintype "passive"))
    )
    (net (code "106") (name "Net-(LED3-PadA)") (class "Default")
      (node (ref "LED3") (pin "A") (pinfunction "A_A") (pintype "passive"))
      (node (ref "R_LED3") (pin "1") (pinfunction "1_1") (pintype "passive"))
    )
    (net (code "107") (name "Net-(LED4-PadA)") (class "Default")
      (node (ref "LED4") (pin "A") (pinfunction "A_A") (pintype "passive"))
      (node (ref "R_LED4") (pin "1") (pinfunction "1_1") (pintype "passive"))
    )
    (net (code "108") (name "Net-(POWER-PadA)") (class "Default")
      (node (ref "POWER") (pin "A") (pinfunction "A_A") (pintype "passive"))
      (node (ref "R_USB3") (pin "1") (pinfunction "1_1") (pintype "passive"))
    )
    (net (code "109") (name "Net-(POWER1-PadA)") (class "Default")
      (node (ref "POWER1") (pin "A") (pinfunction "A_A") (pintype "passive"))
      (node (ref "R_USB4") (pin "1") (pinfunction "1_1") (pintype "passive"))
    )
    (net (code "110") (name "Net-(R_USB5-Pad1)") (class "Default")
      (node (ref "R_USB5") (pin "1") (pinfunction "1_1") (pintype "passive"))
      (node (ref "X2") (pin "2") (pinfunction "2_2") (pintype "passive"))
    )
    (net (code "111") (name "Net-(R_USB6-Pad1)") (class "Default")
      (node (ref "R_USB6") (pin "1") (pinfunction "1_1") (pintype "passive"))
      (node (ref "X2") (pin "3") (pinfunction "3_3") (pintype "passive"))
    )
    (net (code "112") (name "Net-(TLV6002A-+IN)") (class "Default")
      (node (ref "R_REF1") (pin "1") (pinfunction "1_1") (pintype "passive"))
      (node (ref "R_REF2") (pin "1") (pinfunction "1_1") (pintype "passive"))
      (node (ref "TLV6002") (pin "3") (pinfunction "+IN_3") (pintype "input"))
      (node (ref "V_REF") (pin "1") (pinfunction "C_1") (pintype "passive"))
    )
    (net (code "113") (name "UART4_RX") (class "Default")
      (node (ref "IC1") (pin "1") (pinfunction "TXD_1") (pintype "output"))
      (node (ref "MCU1") (pin "114") (pinfunction "PD2_114") (pintype "bidirectional"))
    )
    (net (code "114") (name "UART4_TX") (class "Default")
      (node (ref "IC1") (pin "4") (pinfunction "RXD_4") (pintype "input"))
      (node (ref "MCU1") (pin "115") (pinfunction "PD3_115") (pintype "bidirectional"))
    )
    (net (code "115") (name "VDD_3V3") (class "Default")
      (node (ref "CON2") (pin "33") (pinfunction "33_33") (pintype "passive"))
      (node (ref "C_USB10") (pin "2") (pinfunction "2_2") (pintype "passive"))
      (node (ref "C_USB9") (pin "2") (pinfunction "2_2") (pintype "passive"))
      (node (ref "C_VDD_3V3_1") (pin "1") (pinfunction "1_1") (pintype "passive"))
      (node (ref "C_VDD_3V3_2") (pin "1") (pinfunction "1_1") (pintype "passive"))
      (node (ref "IC1") (pin "12") (pinfunction "VCC_12") (pintype "power_in"))
      (node (ref "MCU1") (pin "108") (pinfunction "PA15_108") (pintype "bidirectional"))
      (node (ref "MCU1") (pin "121") (pinfunction "PD7_121") (pintype "bidirectional"))
      (node (ref "MCU1") (pin "131") (pinfunction "PB4_131") (pintype "bidirectional"))
      (node (ref "MCU1") (pin "144") (pinfunction "VDD_144") (pintype "bidirectional"))
      (node (ref "MCU1") (pin "17") (pinfunction "VFBSMPS_17") (pintype "bidirectional"))
      (node (ref "MCU1") (pin "30") (pinfunction "PC2_C_30") (pintype "bidirectional"))
      (node (ref "MCU1") (pin "33") (pinfunction "VSS_33") (pintype "bidirectional"))
      (node (ref "MCU1") (pin "39") (pinfunction "PA2_39") (pintype "bidirectional"))
      (node (ref "MCU1") (pin "52") (pinfunction "PF11_52") (pintype "bidirectional"))
      (node (ref "MCU1") (pin "6") (pinfunction "VSS_6") (pintype "bidirectional"))
      (node (ref "MCU1") (pin "62") (pinfunction "PE12_62") (pintype "bidirectional"))
      (node (ref "MCU1") (pin "72") (pinfunction "PB12_72") (pintype "bidirectional"))
      (node (ref "MCU1") (pin "84") (pinfunction "PD14_84") (pintype "bidirectional"))
      (node (ref "MCU1") (pin "95") (pinfunction "PC8_95") (pintype "bidirectional"))
      (node (ref "MCU_C1") (pin "1") (pinfunction "1_1") (pintype "passive"))
      (node (ref "MCU_C2") (pin "1") (pinfunction "1_1") (pintype "passive"))
      (node (ref "MCU_C3") (pin "1") (pinfunction "1_1") (pintype "passive"))
      (node (ref "MCU_C4") (pin "1") (pinfunction "1_1") (pintype "passive"))
      (node (ref "MCU_C5") (pin "1") (pinfunction "1_1") (pintype "passive"))
      (node (ref "MCU_C6") (pin "1") (pinfunction "1_1") (pintype "passive"))
      (node (ref "MCU_C7") (pin "1") (pinfunction "1_1") (pintype "passive"))
      (node (ref "MCU_USB_C") (pin "1") (pinfunction "1_1") (pintype "passive"))
      (node (ref "MCU_VDDA_C1") (pin "1") (pinfunction "1_1") (pintype "passive"))
      (node (ref "MCU_VDDA_C2") (pin "1") (pinfunction "1_1") (pintype "passive"))
      (node (ref "NRST_R") (pin "2") (pinfunction "2_2") (pintype "passive"))
      (node (ref "R_REF1") (pin "2") (pinfunction "2_2") (pintype "passive"))
      (node (ref "SWD") (pin "1") (pinfunction "1_1") (pintype "passive"))
      (node (ref "TLV6002") (pin "8") (pinfunction "V+_8") (pintype "power_in"))
      (node (ref "VREG1") (pin "3") (pinfunction "VO_3") (pintype "bidirectional"))
    )
    (net (code "116") (name "VDD_5V") (class "Default")
      (node (ref "CON1") (pin "49") (pinfunction "49_49") (pintype "passive"))
      (node (ref "CON2") (pin "2") (pinfunction "2_2") (pintype "passive"))
      (node (ref "D_POWER") (pin "A") (pinfunction "A_A") (pintype "passive"))
    )
    (net (code "117") (name "unconnected-(IC1-CBUS0-Pad15)") (class "Default")
      (node (ref "IC1") (pin "15") (pinfunction "CBUS0_15") (pintype "bidirectional"))
    )
    (net (code "118") (name "unconnected-(IC1-CBUS1-Pad14)") (class "Default")
      (node (ref "IC1") (pin "14") (pinfunction "CBUS1_14") (pintype "bidirectional"))
    )
    (net (code "119") (name "unconnected-(IC1-CBUS2-Pad7)") (class "Default")
      (node (ref "IC1") (pin "7") (pinfunction "CBUS2_7") (pintype "bidirectional"))
    )
    (net (code "120") (name "unconnected-(IC1-CBUS3-Pad16)") (class "Default")
      (node (ref "IC1") (pin "16") (pinfunction "CBUS3_16") (pintype "bidirectional"))
    )
    (net (code "121") (name "unconnected-(IC1-~{CTS}-Pad6)") (class "Default")
      (node (ref "IC1") (pin "6") (pinfunction "~{CTS}_6") (pintype "input"))
    )
    (net (code "122") (name "unconnected-(IC1-~{RTS}-Pad2)") (class "Default")
      (node (ref "IC1") (pin "2") (pinfunction "~{RTS}_2") (pintype "output"))
    )
    (net (code "123") (name "unconnected-(MCU1-BOOT0-Pad135)") (class "Default")
      (node (ref "MCU1") (pin "135") (pinfunction "BOOT0_135") (pintype "bidirectional"))
    )
    (net (code "124") (name "unconnected-(MCU1-PA10-Pad99)") (class "Default")
      (node (ref "MCU1") (pin "99") (pinfunction "PA10_99") (pintype "bidirectional"))
    )
    (net (code "125") (name "unconnected-(MCU1-PA11-Pad100)") (class "Default")
      (node (ref "MCU1") (pin "100") (pinfunction "PA11_100") (pintype "bidirectional"))
    )
    (net (code "126") (name "unconnected-(MCU1-PA12-Pad101)") (class "Default")
      (node (ref "MCU1") (pin "101") (pinfunction "PA12_101") (pintype "bidirectional"))
    )
    (net (code "127") (name "unconnected-(MCU1-PA13-Pad102)") (class "Default")
      (node (ref "MCU1") (pin "102") (pinfunction "PA13_102") (pintype "bidirectional"))
    )
    (net (code "128") (name "unconnected-(MCU1-PB5-Pad132)") (class "Default")
      (node (ref "MCU1") (pin "132") (pinfunction "PB5_132") (pintype "bidirectional"))
    )
    (net (code "129") (name "unconnected-(MCU1-PB8-Pad136)") (class "Default")
      (node (ref "MCU1") (pin "136") (pinfunction "PB8_136") (pintype "bidirectional"))
    )
    (net (code "130") (name "unconnected-(MCU1-PB9-Pad137)") (class "Default")
      (node (ref "MCU1") (pin "137") (pinfunction "PB9_137") (pintype "bidirectional"))
    )
    (net (code "131") (name "unconnected-(MCU1-PB11-Pad67)") (class "Default")
      (node (ref "MCU1") (pin "67") (pinfunction "PB11_67") (pintype "bidirectional"))
    )
    (net (code "132") (name "unconnected-(MCU1-PC5-Pad48)") (class "Default")
      (node (ref "MCU1") (pin "48") (pinfunction "PC5_48") (pintype "bidirectional"))
    )
    (net (code "133") (name "unconnected-(MCU1-PC6-Pad93)") (class "Default")
      (node (ref "MCU1") (pin "93") (pinfunction "PC6_93") (pintype "bidirectional"))
    )
    (net (code "134") (name "unconnected-(MCU1-PC11-Pad110)") (class "Default")
      (node (ref "MCU1") (pin "110") (pinfunction "PC11_110") (pintype "bidirectional"))
    )
    (net (code "135") (name "unconnected-(MCU1-PC13-Pad9)") (class "Default")
      (node (ref "MCU1") (pin "9") (pinfunction "PC13_9") (pintype "bidirectional"))
    )
    (net (code "136") (name "unconnected-(MCU1-PC14-OSC32_IN-Pad10)") (class "Default")
      (node (ref "MCU1") (pin "10") (pinfunction "PC14-OSC32_IN_10") (pintype "bidirectional"))
    )
    (net (code "137") (name "unconnected-(MCU1-PC15-OSC32_OUT-Pad11)") (class "Default")
      (node (ref "MCU1") (pin "11") (pinfunction "PC15-OSC32_OUT_11") (pintype "bidirectional"))
    )
    (net (code "138") (name "unconnected-(MCU1-PD4-Pad116)") (class "Default")
      (node (ref "MCU1") (pin "116") (pinfunction "PD4_116") (pintype "bidirectional"))
    )
    (net (code "139") (name "unconnected-(MCU1-PD5-Pad117)") (class "Default")
      (node (ref "MCU1") (pin "117") (pinfunction "PD5_117") (pintype "bidirectional"))
    )
    (net (code "140") (name "unconnected-(MCU1-PD9-Pad77)") (class "Default")
      (node (ref "MCU1") (pin "77") (pinfunction "PD9_77") (pintype "bidirectional"))
    )
    (net (code "141") (name "unconnected-(MCU1-PD15-Pad85)") (class "Default")
      (node (ref "MCU1") (pin "85") (pinfunction "PD15_85") (pintype "bidirectional"))
    )
    (net (code "142") (name "unconnected-(MCU1-PDR_ON-Pad142)") (class "Default")
      (node (ref "MCU1") (pin "142") (pinfunction "PDR_ON_142") (pintype "bidirectional"))
    )
    (net (code "143") (name "unconnected-(MCU1-PE0-Pad138)") (class "Default")
      (node (ref "MCU1") (pin "138") (pinfunction "PE0_138") (pintype "bidirectional"))
    )
    (net (code "144") (name "unconnected-(MCU1-PE1-Pad139)") (class "Default")
      (node (ref "MCU1") (pin "139") (pinfunction "PE1_139") (pintype "bidirectional"))
    )
    (net (code "145") (name "unconnected-(MCU1-PE2-Pad1)") (class "Default")
      (node (ref "MCU1") (pin "1") (pinfunction "PE2_1") (pintype "bidirectional"))
    )
    (net (code "146") (name "unconnected-(MCU1-PE3-Pad2)") (class "Default")
      (node (ref "MCU1") (pin "2") (pinfunction "PE3_2") (pintype "bidirectional"))
    )
    (net (code "147") (name "unconnected-(MCU1-PE4-Pad3)") (class "Default")
      (node (ref "MCU1") (pin "3") (pinfunction "PE4_3") (pintype "bidirectional"))
    )
    (net (code "148") (name "unconnected-(MCU1-PE5-Pad4)") (class "Default")
      (node (ref "MCU1") (pin "4") (pinfunction "PE5_4") (pintype "bidirectional"))
    )
    (net (code "149") (name "unconnected-(MCU1-PE6-Pad5)") (class "Default")
      (node (ref "MCU1") (pin "5") (pinfunction "PE6_5") (pintype "bidirectional"))
    )
    (net (code "150") (name "unconnected-(MCU1-PE7-Pad57)") (class "Default")
      (node (ref "MCU1") (pin "57") (pinfunction "PE7_57") (pintype "bidirectional"))
    )
    (net (code "151") (name "unconnected-(MCU1-PE8-Pad58)") (class "Default")
      (node (ref "MCU1") (pin "58") (pinfunction "PE8_58") (pintype "bidirectional"))
    )
    (net (code "152") (name "unconnected-(MCU1-PF9-Pad23)") (class "Default")
      (node (ref "MCU1") (pin "23") (pinfunction "PF9_23") (pintype "bidirectional"))
    )
    (net (code "153") (name "unconnected-(MCU1-PF10-Pad24)") (class "Default")
      (node (ref "MCU1") (pin "24") (pinfunction "PF10_24") (pintype "bidirectional"))
    )
    (net (code "154") (name "unconnected-(MCU1-PG6-Pad86)") (class "Default")
      (node (ref "MCU1") (pin "86") (pinfunction "PG6_86") (pintype "bidirectional"))
    )
    (net (code "155") (name "unconnected-(MCU1-PG11-Pad124)") (class "Default")
      (node (ref "MCU1") (pin "124") (pinfunction "PG11_124") (pintype "bidirectional"))
    )
    (net (code "156") (name "unconnected-(MCU1-PG12-Pad125)") (class "Default")
      (node (ref "MCU1") (pin "125") (pinfunction "PG12_125") (pintype "bidirectional"))
    )
    (net (code "157") (name "unconnected-(MCU1-VBAT-Pad8)") (class "Default")
      (node (ref "MCU1") (pin "8") (pinfunction "VBAT_8") (pintype "bidirectional"))
    )
    (net (code "158") (name "unconnected-(MCU1-VCAP-Pad103)") (class "Default")
      (node (ref "MCU1") (pin "103") (pinfunction "VCAP_103") (pintype "bidirectional"))
    )
    (net (code "159") (name "unconnected-(MCU1-VCAP-Pad140)") (class "Default")
      (node (ref "MCU1") (pin "140") (pinfunction "VCAP_140") (pintype "bidirectional"))
    )
    (net (code "160") (name "unconnected-(MCU1-VDD-Pad7)") (class "Default")
      (node (ref "MCU1") (pin "7") (pinfunction "VDD_7") (pintype "bidirectional"))
    )
    (net (code "161") (name "unconnected-(MCU1-VDD-Pad42)") (class "Default")
      (node (ref "MCU1") (pin "42") (pinfunction "VDD_42") (pintype "bidirectional"))
    )
    (net (code "162") (name "unconnected-(MCU1-VDD-Pad56)") (class "Default")
      (node (ref "MCU1") (pin "56") (pinfunction "VDD_56") (pintype "bidirectional"))
    )
    (net (code "163") (name "unconnected-(MCU1-VDD-Pad92)") (class "Default")
      (node (ref "MCU1") (pin "92") (pinfunction "VDD_92") (pintype "bidirectional"))
    )
    (net (code "164") (name "unconnected-(MCU1-VDD-Pad119)") (class "Default")
      (node (ref "MCU1") (pin "119") (pinfunction "VDD_119") (pintype "bidirectional"))
    )
    (net (code "165") (name "unconnected-(MCU1-VDD33USB-Pad91)") (class "Default")
      (node (ref "MCU1") (pin "91") (pinfunction "VDD33USB_91") (pintype "bidirectional"))
    )
    (net (code "166") (name "unconnected-(MCU1-VDD50USB-Pad90)") (class "Default")
      (node (ref "MCU1") (pin "90") (pinfunction "VDD50USB_90") (pintype "bidirectional"))
    )
    (net (code "167") (name "unconnected-(MCU1-VDDA-Pad36)") (class "Default")
      (node (ref "MCU1") (pin "36") (pinfunction "VDDA_36") (pintype "bidirectional"))
    )
    (net (code "168") (name "unconnected-(MCU1-VDDLDO-Pad70)") (class "Default")
      (node (ref "MCU1") (pin "70") (pinfunction "VDDLDO_70") (pintype "bidirectional"))
    )
    (net (code "169") (name "unconnected-(MCU1-VSS-Pad12)") (class "Default")
      (node (ref "MCU1") (pin "12") (pinfunction "VSS_12") (pintype "bidirectional"))
    )
    (net (code "170") (name "unconnected-(MCU1-VSS-Pad69)") (class "Default")
      (node (ref "MCU1") (pin "69") (pinfunction "VSS_69") (pintype "bidirectional"))
    )
    (net (code "171") (name "unconnected-(MCU1-VSS-Pad80)") (class "Default")
      (node (ref "MCU1") (pin "80") (pinfunction "VSS_80") (pintype "bidirectional"))
    )
    (net (code "172") (name "unconnected-(MCU1-VSS-Pad104)") (class "Default")
      (node (ref "MCU1") (pin "104") (pinfunction "VSS_104") (pintype "bidirectional"))
    )
    (net (code "173") (name "unconnected-(MCU1-VSS-Pad118)") (class "Default")
      (node (ref "MCU1") (pin "118") (pinfunction "VSS_118") (pintype "bidirectional"))
    )
    (net (code "174") (name "unconnected-(MCU1-VSS-Pad141)") (class "Default")
      (node (ref "MCU1") (pin "141") (pinfunction "VSS_141") (pintype "bidirectional"))
    )
  )
)
